# Amplifier_Left.net
KiCad netlist of a schematic drawn in Altium Designer
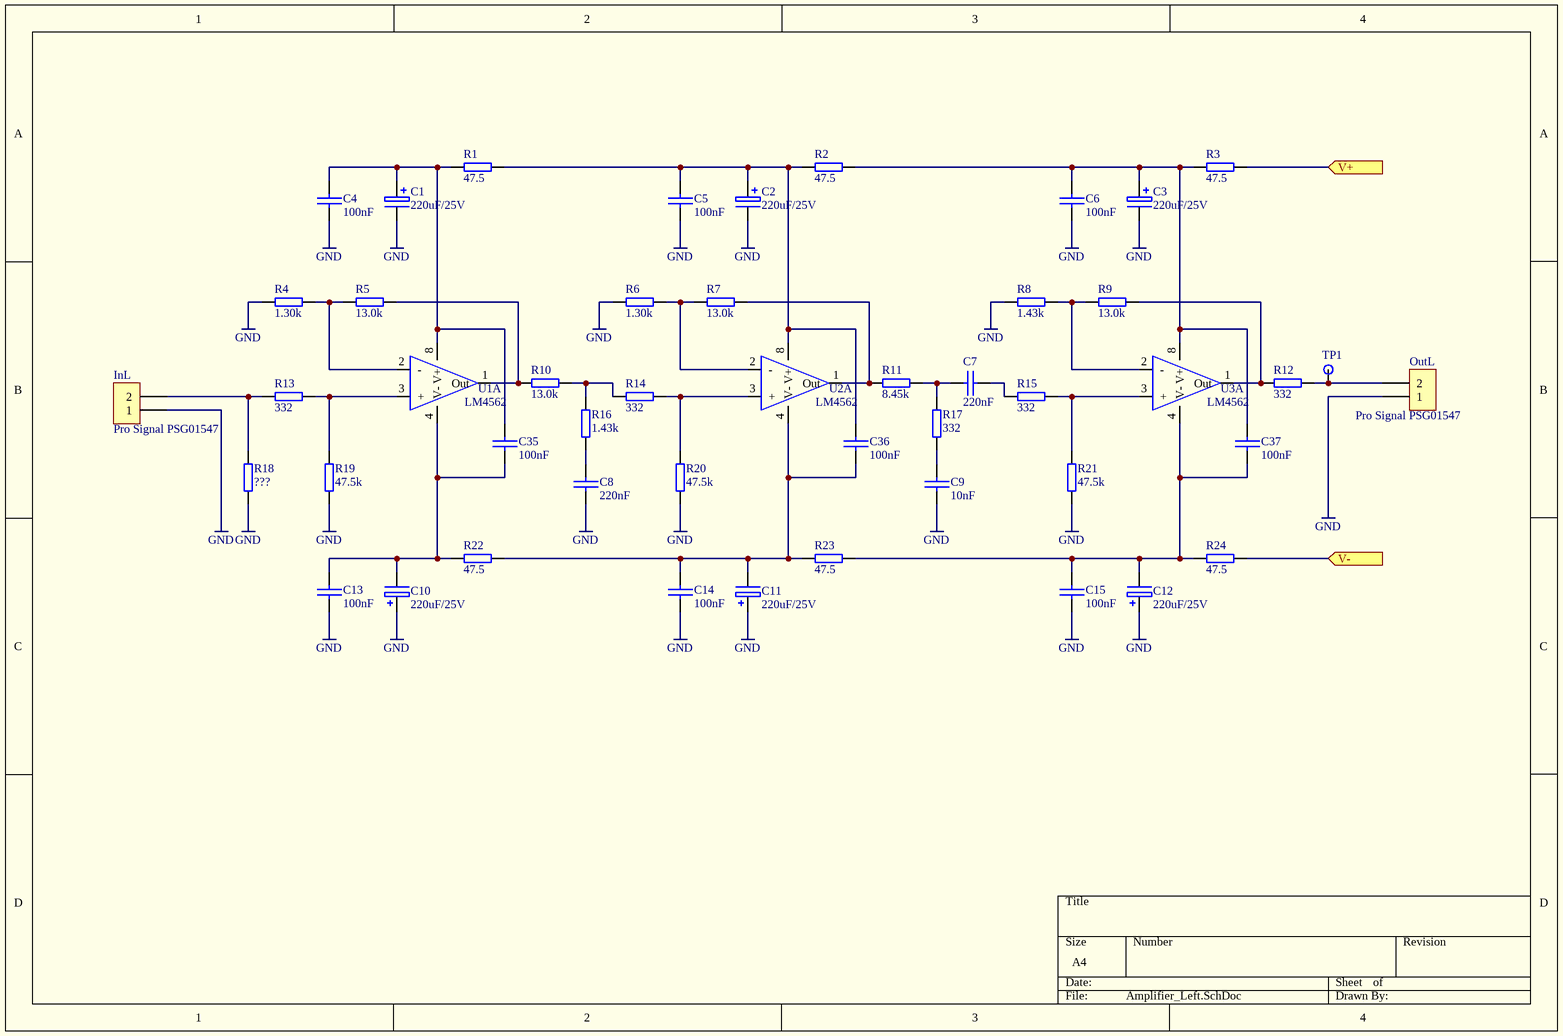
[diagram p0: Amplifier_Left.SchDoc]

(export (version "E")
  (design (tool "Eeschema 10.0.6"))
  (components
    (comp (ref "C1")
      (value "220uF/25V")
      (footprint "CAP_EC8x16")
      (description "Electrolytic Capacitor")
      (libsource (lib "*") (part "ELECTRO1"))
    )
    (comp (ref "C2")
      (value "220uF/25V")
      (footprint "CAP_EC8x16")
      (description "Electrolytic Capacitor")
      (libsource (lib "*") (part "ELECTRO1"))
    )
    (comp (ref "C3")
      (value "220uF/25V")
      (footprint "CAP_EC8x16")
      (description "Electrolytic Capacitor")
      (libsource (lib "*") (part "ELECTRO1"))
    )
    (comp (ref "C4")
      (value "100nF")
      (footprint "CAP_C200")
      (description "Capacitor")
      (libsource (lib "*") (part "CAP"))
    )
    (comp (ref "C5")
      (value "100nF")
      (footprint "CAP_C200")
      (description "Capacitor")
      (libsource (lib "*") (part "CAP"))
    )
    (comp (ref "C6")
      (value "100nF")
      (footprint "CAP_C200")
      (description "Capacitor")
      (libsource (lib "*") (part "CAP"))
    )
    (comp (ref "C7")
      (value "220nF")
      (footprint "CAP_C200-1")
      (description "Capacitor")
      (libsource (lib "*") (part "CAP"))
    )
    (comp (ref "C8")
      (value "220nF")
      (footprint "CAP_C200-1")
      (description "Capacitor")
      (libsource (lib "*") (part "CAP"))
    )
    (comp (ref "C9")
      (value "10nF")
      (footprint "CAP_C200")
      (description "Capacitor")
      (libsource (lib "*") (part "CAP"))
    )
    (comp (ref "C10")
      (value "220uF/25V")
      (footprint "CAP_EC8x16")
      (description "Electrolytic Capacitor")
      (libsource (lib "*") (part "ELECTRO1"))
    )
    (comp (ref "C11")
      (value "220uF/25V")
      (footprint "CAP_EC8x16")
      (description "Electrolytic Capacitor")
      (libsource (lib "*") (part "ELECTRO1"))
    )
    (comp (ref "C12")
      (value "220uF/25V")
      (footprint "CAP_EC8x16")
      (description "Electrolytic Capacitor")
      (libsource (lib "*") (part "ELECTRO1"))
    )
    (comp (ref "C13")
      (value "100nF")
      (footprint "CAP_C200")
      (description "Capacitor")
      (libsource (lib "*") (part "CAP"))
    )
    (comp (ref "C14")
      (value "100nF")
      (footprint "CAP_C200")
      (description "Capacitor")
      (libsource (lib "*") (part "CAP"))
    )
    (comp (ref "C15")
      (value "100nF")
      (footprint "CAP_C200")
      (description "Capacitor")
      (libsource (lib "*") (part "CAP"))
    )
    (comp (ref "C35")
      (value "100nF")
      (footprint "CAP_C200")
      (description "Capacitor")
      (libsource (lib "*") (part "CAP"))
    )
    (comp (ref "C36")
      (value "100nF")
      (footprint "CAP_C200")
      (description "Capacitor")
      (libsource (lib "*") (part "CAP"))
    )
    (comp (ref "C37")
      (value "100nF")
      (footprint "CAP_C200")
      (description "Capacitor")
      (libsource (lib "*") (part "CAP"))
    )
    (comp (ref "InL")
      (value "Pro Signal PSG01547")
      (footprint "CON_RCA_PSG01547")
      (description "Connector")
      (libsource (lib "*") (part "CON2"))
    )
    (comp (ref "OutL")
      (value "Pro Signal PSG01547")
      (footprint "CON_RCA_PSG01547")
      (description "Connector")
      (libsource (lib "") (part "CON2_1"))
    )
    (comp (ref "R1")
      (value "47.5")
      (footprint "RES_R400")
      (description "Resistor")
      (libsource (lib "MainSchlib") (part "RES"))
    )
    (comp (ref "R2")
      (value "47.5")
      (footprint "RES_R400")
      (description "Resistor")
      (libsource (lib "MainSchlib") (part "RES"))
    )
    (comp (ref "R3")
      (value "47.5")
      (footprint "RES_R400")
      (description "Resistor")
      (libsource (lib "MainSchlib") (part "RES"))
    )
    (comp (ref "R4")
      (value "1.30k")
      (footprint "RES_R400")
      (description "Resistor")
      (libsource (lib "MainSchlib") (part "RES"))
    )
    (comp (ref "R5")
      (value "13.0k")
      (footprint "RES_R400")
      (description "Resistor")
      (libsource (lib "MainSchlib") (part "RES"))
    )
    (comp (ref "R6")
      (value "1.30k")
      (footprint "RES_R400")
      (description "Resistor")
      (libsource (lib "MainSchlib") (part "RES"))
    )
    (comp (ref "R7")
      (value "13.0k")
      (footprint "RES_R400")
      (description "Resistor")
      (libsource (lib "MainSchlib") (part "RES"))
    )
    (comp (ref "R8")
      (value "1.43k")
      (footprint "RES_R400")
      (description "Resistor")
      (libsource (lib "MainSchlib") (part "RES"))
    )
    (comp (ref "R9")
      (value "13.0k")
      (footprint "RES_R400")
      (description "Resistor")
      (libsource (lib "MainSchlib") (part "RES"))
    )
    (comp (ref "R10")
      (value "13.0k")
      (footprint "RES_R400")
      (description "Resistor")
      (libsource (lib "MainSchlib") (part "RES"))
    )
    (comp (ref "R11")
      (value "8.45k")
      (footprint "RES_R400")
      (description "Resistor")
      (libsource (lib "MainSchlib") (part "RES"))
    )
    (comp (ref "R12")
      (value "332")
      (footprint "RES_R400")
      (description "Resistor")
      (libsource (lib "MainSchlib") (part "RES"))
    )
    (comp (ref "R13")
      (value "332")
      (footprint "RES_R400")
      (description "Resistor")
      (libsource (lib "MainSchlib") (part "RES"))
    )
    (comp (ref "R14")
      (value "332")
      (footprint "RES_R400")
      (description "Resistor")
      (libsource (lib "MainSchlib") (part "RES"))
    )
    (comp (ref "R15")
      (value "332")
      (footprint "RES_R400")
      (description "Resistor")
      (libsource (lib "MainSchlib") (part "RES"))
    )
    (comp (ref "R16")
      (value "1.43k")
      (footprint "RES_R400")
      (description "Resistor")
      (libsource (lib "MainSchlib") (part "RES"))
    )
    (comp (ref "R17")
      (value "332")
      (footprint "RES_R400")
      (description "Resistor")
      (libsource (lib "MainSchlib") (part "RES"))
    )
    (comp (ref "R18")
      (value "???")
      (footprint "RES_R400")
      (description "Resistor")
      (libsource (lib "MainSchlib") (part "RES"))
    )
    (comp (ref "R19")
      (value "47.5k")
      (footprint "RES_R400")
      (description "Resistor")
      (libsource (lib "MainSchlib") (part "RES"))
    )
    (comp (ref "R20")
      (value "47.5k")
      (footprint "RES_R400")
      (description "Resistor")
      (libsource (lib "MainSchlib") (part "RES"))
    )
    (comp (ref "R21")
      (value "47.5k")
      (footprint "RES_R400")
      (description "Resistor")
      (libsource (lib "MainSchlib") (part "RES"))
    )
    (comp (ref "R22")
      (value "47.5")
      (footprint "RES_R400")
      (description "Resistor")
      (libsource (lib "MainSchlib") (part "RES"))
    )
    (comp (ref "R23")
      (value "47.5")
      (footprint "RES_R400")
      (description "Resistor")
      (libsource (lib "MainSchlib") (part "RES"))
    )
    (comp (ref "R24")
      (value "47.5")
      (footprint "RES_R400")
      (description "Resistor")
      (libsource (lib "MainSchlib") (part "RES"))
    )
    (comp (ref "TP1")
      (value "TESTPAD")
      (footprint "MISC_PAD-36/65")
      (libsource (lib "MainSchlib") (part "TESTPAD"))
    )
    (comp (ref "U1")
      (value "LM4562")
      (footprint "IC_DIP-8")
      (description "standard dual op-amp")
      (libsource (lib "MainSchlib") (part "OPAMP_Dual"))
    )
    (comp (ref "U2")
      (value "LM4562")
      (footprint "IC_DIP-8")
      (description "standard dual op-amp")
      (libsource (lib "MainSchlib") (part "OPAMP_Dual"))
    )
    (comp (ref "U3")
      (value "LM4562")
      (footprint "IC_DIP-8")
      (description "standard dual op-amp")
      (libsource (lib "MainSchlib") (part "OPAMP_Dual"))
    )
  )
  (nets
    (net (code "1") (name "/V+") (class "Default") (node (ref "R3") (pin "1") (pintype "passive")))
    (net (code "2") (name "/V-") (class "Default") (node (ref "R24") (pin "1") (pintype "passive")))
    (net (code "3") (name "GND") (class "Default")
      (node (ref "C1") (pin "2") (pinfunction "2_2") (pintype "passive"))
      (node (ref "C10") (pin "1") (pinfunction "1_1") (pintype "passive"))
      (node (ref "C11") (pin "1") (pinfunction "1_1") (pintype "passive"))
      (node (ref "C12") (pin "1") (pinfunction "1_1") (pintype "passive"))
      (node (ref "C13") (pin "2") (pinfunction "2_2") (pintype "passive"))
      (node (ref "C14") (pin "2") (pinfunction "2_2") (pintype "passive"))
      (node (ref "C15") (pin "2") (pinfunction "2_2") (pintype "passive"))
      (node (ref "C2") (pin "2") (pinfunction "2_2") (pintype "passive"))
      (node (ref "C3") (pin "2") (pinfunction "2_2") (pintype "passive"))
      (node (ref "C4") (pin "2") (pinfunction "2_2") (pintype "passive"))
      (node (ref "C5") (pin "2") (pinfunction "2_2") (pintype "passive"))
      (node (ref "C6") (pin "2") (pinfunction "2_2") (pintype "passive"))
      (node (ref "C8") (pin "2") (pinfunction "2_2") (pintype "passive"))
      (node (ref "C9") (pin "2") (pinfunction "2_2") (pintype "passive"))
      (node (ref "InL") (pin "1") (pinfunction "1_1") (pintype "passive"))
      (node (ref "OutL") (pin "1") (pinfunction "1_1") (pintype "passive"))
      (node (ref "R18") (pin "1") (pintype "passive"))
      (node (ref "R19") (pin "2") (pintype "passive"))
      (node (ref "R20") (pin "2") (pintype "passive"))
      (node (ref "R21") (pin "2") (pintype "passive"))
      (node (ref "R4") (pin "2") (pintype "passive"))
      (node (ref "R6") (pin "2") (pintype "passive"))
      (node (ref "R8") (pin "2") (pintype "passive"))
    )
    (net (code "4") (name "Net-(C7-Pad1)") (class "Default")
      (node (ref "C7") (pin "1") (pinfunction "1_1") (pintype "passive"))
      (node (ref "R11") (pin "1") (pintype "passive"))
      (node (ref "R17") (pin "1") (pintype "passive"))
    )
    (net (code "5") (name "Net-(C7-Pad2)") (class "Default")
      (node (ref "C7") (pin "2") (pinfunction "2_2") (pintype "passive"))
      (node (ref "R15") (pin "2") (pintype "passive"))
    )
    (net (code "6") (name "Net-(C8-Pad1)") (class "Default")
      (node (ref "C8") (pin "1") (pinfunction "1_1") (pintype "passive"))
      (node (ref "R16") (pin "2") (pintype "passive"))
    )
    (net (code "7") (name "Net-(C9-Pad1)") (class "Default")
      (node (ref "C9") (pin "1") (pinfunction "1_1") (pintype "passive"))
      (node (ref "R17") (pin "2") (pintype "passive"))
    )
    (net (code "8") (name "Net-(InL-Pad2)") (class "Default")
      (node (ref "InL") (pin "2") (pinfunction "2_2") (pintype "passive"))
      (node (ref "R13") (pin "2") (pintype "passive"))
      (node (ref "R18") (pin "2") (pintype "passive"))
    )
    (net (code "9") (name "Net-(OutL-Pad2)") (class "Default")
      (node (ref "OutL") (pin "2") (pinfunction "2_2") (pintype "passive"))
      (node (ref "R12") (pin "1") (pintype "passive"))
      (node (ref "TP1") (pin "1") (pinfunction "1_1") (pintype "passive"))
    )
    (net (code "10") (name "Net-(R10-Pad1)") (class "Default")
      (node (ref "R10") (pin "1") (pintype "passive"))
      (node (ref "R14") (pin "2") (pintype "passive"))
      (node (ref "R16") (pin "1") (pintype "passive"))
    )
    (net (code "11") (name "Net-(U1A-+)") (class "Default")
      (node (ref "R13") (pin "1") (pintype "passive"))
      (node (ref "R19") (pin "1") (pintype "passive"))
      (node (ref "U1") (pin "3") (pinfunction "+_3") (pintype "passive"))
    )
    (net (code "12") (name "Net-(U1A--)") (class "Default")
      (node (ref "R4") (pin "1") (pintype "passive"))
      (node (ref "R5") (pin "2") (pintype "passive"))
      (node (ref "U1") (pin "2") (pinfunction "-_2") (pintype "passive"))
    )
    (net (code "13") (name "Net-(U1A-Out)") (class "Default")
      (node (ref "R10") (pin "2") (pintype "passive"))
      (node (ref "R5") (pin "1") (pintype "passive"))
      (node (ref "U1") (pin "1") (pinfunction "Out_1") (pintype "passive"))
    )
    (net (code "14") (name "Net-(U1A-V+)") (class "Default")
      (node (ref "C1") (pin "1") (pinfunction "1_1") (pintype "passive"))
      (node (ref "C35") (pin "1") (pinfunction "1_1") (pintype "passive"))
      (node (ref "C4") (pin "1") (pinfunction "1_1") (pintype "passive"))
      (node (ref "R1") (pin "2") (pintype "passive"))
      (node (ref "U1") (pin "8") (pinfunction "V+_8") (pintype "passive"))
    )
    (net (code "15") (name "Net-(U1A-V-)") (class "Default")
      (node (ref "C10") (pin "2") (pinfunction "2_2") (pintype "passive"))
      (node (ref "C13") (pin "1") (pinfunction "1_1") (pintype "passive"))
      (node (ref "C35") (pin "2") (pinfunction "2_2") (pintype "passive"))
      (node (ref "R22") (pin "2") (pintype "passive"))
      (node (ref "U1") (pin "4") (pinfunction "V-_4") (pintype "passive"))
    )
    (net (code "16") (name "Net-(U2A-+)") (class "Default")
      (node (ref "R14") (pin "1") (pintype "passive"))
      (node (ref "R20") (pin "1") (pintype "passive"))
      (node (ref "U2") (pin "3") (pinfunction "+_3") (pintype "passive"))
    )
    (net (code "17") (name "Net-(U2A--)") (class "Default")
      (node (ref "R6") (pin "1") (pintype "passive"))
      (node (ref "R7") (pin "2") (pintype "passive"))
      (node (ref "U2") (pin "2") (pinfunction "-_2") (pintype "passive"))
    )
    (net (code "18") (name "Net-(U2A-Out)") (class "Default")
      (node (ref "R11") (pin "2") (pintype "passive"))
      (node (ref "R7") (pin "1") (pintype "passive"))
      (node (ref "U2") (pin "1") (pinfunction "Out_1") (pintype "passive"))
    )
    (net (code "19") (name "Net-(U2A-V+)") (class "Default")
      (node (ref "C2") (pin "1") (pinfunction "1_1") (pintype "passive"))
      (node (ref "C36") (pin "1") (pinfunction "1_1") (pintype "passive"))
      (node (ref "C5") (pin "1") (pinfunction "1_1") (pintype "passive"))
      (node (ref "R1") (pin "1") (pintype "passive"))
      (node (ref "R2") (pin "2") (pintype "passive"))
      (node (ref "U2") (pin "8") (pinfunction "V+_8") (pintype "passive"))
    )
    (net (code "20") (name "Net-(U2A-V-)") (class "Default")
      (node (ref "C11") (pin "2") (pinfunction "2_2") (pintype "passive"))
      (node (ref "C14") (pin "1") (pinfunction "1_1") (pintype "passive"))
      (node (ref "C36") (pin "2") (pinfunction "2_2") (pintype "passive"))
      (node (ref "R22") (pin "1") (pintype "passive"))
      (node (ref "R23") (pin "2") (pintype "passive"))
      (node (ref "U2") (pin "4") (pinfunction "V-_4") (pintype "passive"))
    )
    (net (code "21") (name "Net-(U3A-+)") (class "Default")
      (node (ref "R15") (pin "1") (pintype "passive"))
      (node (ref "R21") (pin "1") (pintype "passive"))
      (node (ref "U3") (pin "3") (pinfunction "+_3") (pintype "passive"))
    )
    (net (code "22") (name "Net-(U3A--)") (class "Default")
      (node (ref "R8") (pin "1") (pintype "passive"))
      (node (ref "R9") (pin "2") (pintype "passive"))
      (node (ref "U3") (pin "2") (pinfunction "-_2") (pintype "passive"))
    )
    (net (code "23") (name "Net-(U3A-Out)") (class "Default")
      (node (ref "R12") (pin "2") (pintype "passive"))
      (node (ref "R9") (pin "1") (pintype "passive"))
      (node (ref "U3") (pin "1") (pinfunction "Out_1") (pintype "passive"))
    )
    (net (code "24") (name "Net-(U3A-V+)") (class "Default")
      (node (ref "C3") (pin "1") (pinfunction "1_1") (pintype "passive"))
      (node (ref "C37") (pin "1") (pinfunction "1_1") (pintype "passive"))
      (node (ref "C6") (pin "1") (pinfunction "1_1") (pintype "passive"))
      (node (ref "R2") (pin "1") (pintype "passive"))
      (node (ref "R3") (pin "2") (pintype "passive"))
      (node (ref "U3") (pin "8") (pinfunction "V+_8") (pintype "passive"))
    )
    (net (code "25") (name "Net-(U3A-V-)") (class "Default")
      (node (ref "C12") (pin "2") (pinfunction "2_2") (pintype "passive"))
      (node (ref "C15") (pin "1") (pinfunction "1_1") (pintype "passive"))
      (node (ref "C37") (pin "2") (pinfunction "2_2") (pintype "passive"))
      (node (ref "R23") (pin "1") (pintype "passive"))
      (node (ref "R24") (pin "2") (pintype "passive"))
      (node (ref "U3") (pin "4") (pinfunction "V-_4") (pintype "passive"))
    )
  )
)
